# Nanite_841_-_Minib_v1_0.net
KiCad netlist of a schematic drawn in EAGLE
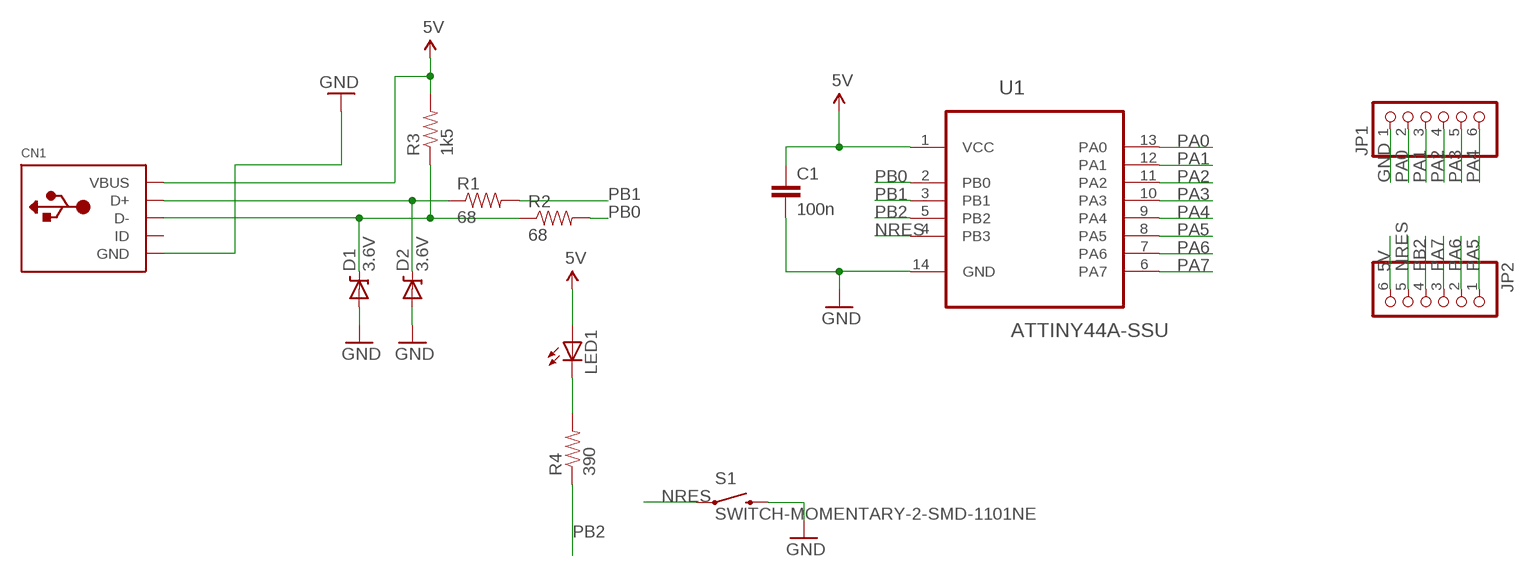
[diagram p0: schematic, sheet 1]

(export (version "E")
  (design (tool "Eeschema 10.0.6"))
  (components
    (comp (ref "C1")
      (value "100n")
      (footprint "eagle-import:0805")
      (libsource (lib "eagle-import") (part "CAP0805"))
    )
    (comp (ref "CN1")
      (value "USBMINIB")
      (footprint "eagle-import:USB-MINIB")
      (libsource (lib "eagle-import") (part "USBMINIB"))
    )
    (comp (ref "D1")
      (value "3.6V")
      (footprint "eagle-import:SOD-323")
      (libsource (lib "eagle-import") (part "DIODE-ZENER-BZT52"))
    )
    (comp (ref "D2")
      (value "3.6V")
      (footprint "eagle-import:SOD-323")
      (libsource (lib "eagle-import") (part "DIODE-ZENER-BZT52"))
    )
    (comp (ref "JP1")
      (value "HEADER-1X6ROUND")
      (footprint "eagle-import:1X06_ROUND")
      (libsource (lib "eagle-import") (part "HEADER-1X6ROUND"))
    )
    (comp (ref "JP2")
      (value "HEADER-1X6ROUND")
      (footprint "eagle-import:1X06_ROUND")
      (libsource (lib "eagle-import") (part "HEADER-1X6ROUND"))
    )
    (comp (ref "LED1")
      (value "LEDCHIPLED_0805")
      (footprint "eagle-import:CHIPLED_0805")
      (libsource (lib "eagle-import") (part "LEDCHIPLED_0805"))
    )
    (comp (ref "R1")
      (value "68")
      (footprint "eagle-import:0805")
      (libsource (lib "eagle-import") (part "RESISTOR0805-RES"))
    )
    (comp (ref "R2")
      (value "68")
      (footprint "eagle-import:0805")
      (libsource (lib "eagle-import") (part "RESISTOR0805-RES"))
    )
    (comp (ref "R3")
      (value "1k5")
      (footprint "eagle-import:0805")
      (libsource (lib "eagle-import") (part "RESISTOR0805-RES"))
    )
    (comp (ref "R4")
      (value "390")
      (footprint "eagle-import:0805")
      (libsource (lib "eagle-import") (part "RESISTOR0805-RES"))
    )
    (comp (ref "S1")
      (value "SWITCH-MOMENTARY-2-SMD-1101NE")
      (footprint "eagle-import:TACTILE-SWITCH-1101NE")
      (libsource (lib "eagle-import") (part "SWITCH-MOMENTARY-2-SMD-1101NE"))
    )
    (comp (ref "U1")
      (value "ATTINY44A-SSU")
      (footprint "eagle-import:SOIC127P600X175-14N")
      (libsource (lib "eagle-import") (part "ATTINY44A-SSU"))
    )
  )
  (nets
    (net (code "1") (name "/NRES") (class "Default")
      (node (ref "JP2") (pin "5") (pinfunction "5_5") (pintype "passive"))
      (node (ref "S1") (pin "P$1") (pinfunction "1_P$1") (pintype "passive"))
      (node (ref "U1") (pin "4") (pinfunction "PB3_4") (pintype "bidirectional"))
    )
    (net (code "2") (name "/PA0") (class "Default")
      (node (ref "JP1") (pin "2") (pinfunction "2_2") (pintype "passive"))
      (node (ref "U1") (pin "13") (pinfunction "PA0_13") (pintype "bidirectional"))
    )
    (net (code "3") (name "/PA1") (class "Default")
      (node (ref "JP1") (pin "3") (pinfunction "3_3") (pintype "passive"))
      (node (ref "U1") (pin "12") (pinfunction "PA1_12") (pintype "bidirectional"))
    )
    (net (code "4") (name "/PA2") (class "Default")
      (node (ref "JP1") (pin "4") (pinfunction "4_4") (pintype "passive"))
      (node (ref "U1") (pin "11") (pinfunction "PA2_11") (pintype "bidirectional"))
    )
    (net (code "5") (name "/PA3") (class "Default")
      (node (ref "JP1") (pin "5") (pinfunction "5_5") (pintype "passive"))
      (node (ref "U1") (pin "10") (pinfunction "PA3_10") (pintype "bidirectional"))
    )
    (net (code "6") (name "/PA4") (class "Default")
      (node (ref "JP1") (pin "6") (pinfunction "6_6") (pintype "passive"))
      (node (ref "U1") (pin "9") (pinfunction "PA4_9") (pintype "bidirectional"))
    )
    (net (code "7") (name "/PA5") (class "Default")
      (node (ref "JP2") (pin "1") (pinfunction "1_1") (pintype "passive"))
      (node (ref "U1") (pin "8") (pinfunction "PA5_8") (pintype "bidirectional"))
    )
    (net (code "8") (name "/PA6") (class "Default")
      (node (ref "JP2") (pin "2") (pinfunction "2_2") (pintype "passive"))
      (node (ref "U1") (pin "7") (pinfunction "PA6_7") (pintype "bidirectional"))
    )
    (net (code "9") (name "/PA7") (class "Default")
      (node (ref "JP2") (pin "3") (pinfunction "3_3") (pintype "passive"))
      (node (ref "U1") (pin "6") (pinfunction "PA7_6") (pintype "bidirectional"))
    )
    (net (code "10") (name "/PB0") (class "Default")
      (node (ref "R2") (pin "2") (pinfunction "2_2") (pintype "passive"))
      (node (ref "U1") (pin "2") (pinfunction "PB0_2") (pintype "bidirectional"))
    )
    (net (code "11") (name "/PB1") (class "Default")
      (node (ref "R1") (pin "2") (pinfunction "2_2") (pintype "passive"))
      (node (ref "U1") (pin "3") (pinfunction "PB1_3") (pintype "bidirectional"))
    )
    (net (code "12") (name "/PB2") (class "Default")
      (node (ref "JP2") (pin "4") (pinfunction "4_4") (pintype "passive"))
      (node (ref "R4") (pin "1") (pinfunction "1_1") (pintype "passive"))
      (node (ref "U1") (pin "5") (pinfunction "PB2_5") (pintype "bidirectional"))
    )
    (net (code "13") (name "5V") (class "Default")
      (node (ref "C1") (pin "1") (pinfunction "1_1") (pintype "passive"))
      (node (ref "CN1") (pin "VBUS") (pinfunction "VBUS_VBUS") (pintype "power_in"))
      (node (ref "JP2") (pin "6") (pinfunction "6_6") (pintype "passive"))
      (node (ref "LED1") (pin "A") (pinfunction "A_A") (pintype "passive"))
      (node (ref "R3") (pin "2") (pinfunction "2_2") (pintype "passive"))
      (node (ref "U1") (pin "1") (pinfunction "VCC_1") (pintype "power_in"))
    )
    (net (code "14") (name "GND") (class "Default")
      (node (ref "C1") (pin "2") (pinfunction "2_2") (pintype "passive"))
      (node (ref "CN1") (pin "GND") (pinfunction "GND_GND") (pintype "power_in"))
      (node (ref "D1") (pin "2") (pinfunction "A_2") (pintype "passive"))
      (node (ref "D2") (pin "2") (pinfunction "A_2") (pintype "passive"))
      (node (ref "JP1") (pin "1") (pinfunction "1_1") (pintype "passive"))
      (node (ref "S1") (pin "P$2") (pinfunction "2_P$2") (pintype "passive"))
      (node (ref "U1") (pin "14") (pinfunction "GND_14") (pintype "power_in"))
    )
    (net (code "15") (name "Net-(D1-C)") (class "Default")
      (node (ref "CN1") (pin "D-") (pinfunction "D-_D-") (pintype "bidirectional"))
      (node (ref "D1") (pin "1") (pinfunction "C_1") (pintype "passive"))
      (node (ref "R2") (pin "1") (pinfunction "1_1") (pintype "passive"))
      (node (ref "R3") (pin "1") (pinfunction "1_1") (pintype "passive"))
    )
    (net (code "16") (name "Net-(D2-C)") (class "Default")
      (node (ref "CN1") (pin "D+") (pinfunction "D+_D+") (pintype "bidirectional"))
      (node (ref "D2") (pin "1") (pinfunction "C_1") (pintype "passive"))
      (node (ref "R1") (pin "1") (pinfunction "1_1") (pintype "passive"))
    )
    (net (code "17") (name "Net-(LED1-PadC)") (class "Default")
      (node (ref "LED1") (pin "C") (pinfunction "C_C") (pintype "passive"))
      (node (ref "R4") (pin "2") (pinfunction "2_2") (pintype "passive"))
    )
    (net (code "18") (name "unconnected-(CN1-PadID)") (class "Default")
      (node (ref "CN1") (pin "ID") (pinfunction "ID_ID") (pintype "bidirectional"))
    )
  )
)
